# plcc44-to-dip44.net
KiCad netlist of a schematic drawn in EAGLE
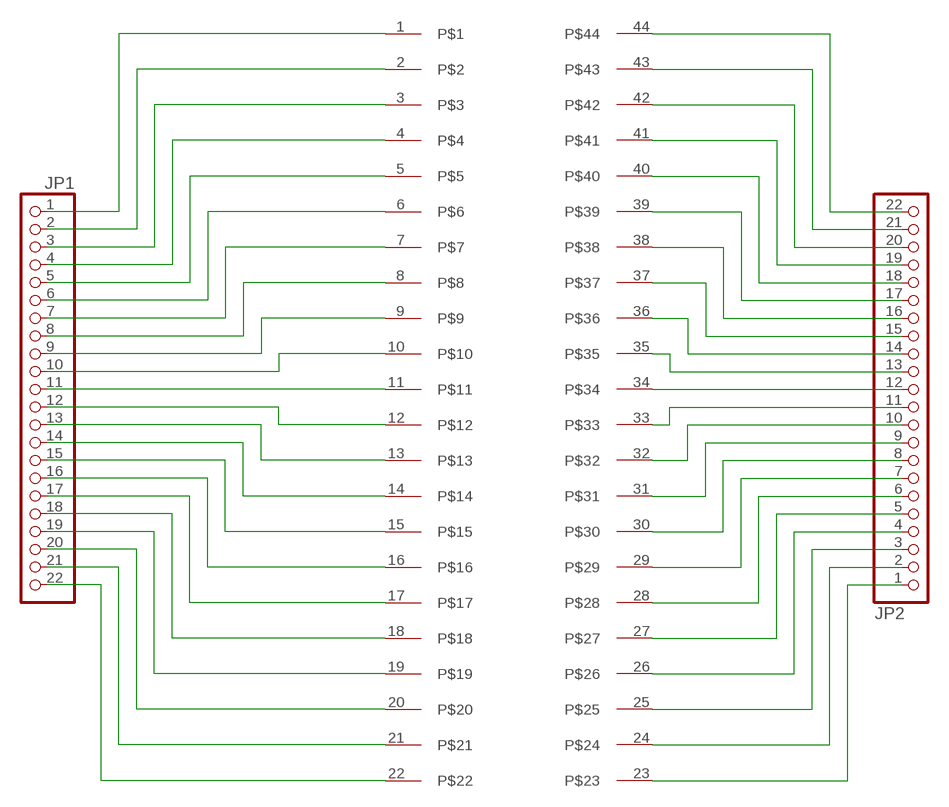
[diagram p0: schematic, sheet 1]

(export (version "E")
  (design (tool "Eeschema 10.0.6"))
  (components
    (comp (ref "JP1")
      (value "PINHD-1X22")
      (footprint "eagle-import:1X22")
      (libsource (lib "eagle-import") (part "PINHD-1X22"))
    )
    (comp (ref "JP2")
      (value "PINHD-1X22")
      (footprint "eagle-import:1X22")
      (libsource (lib "eagle-import") (part "PINHD-1X22"))
    )
    (comp (ref "U$1")
      (value "PLCC44-SOCKET")
      (footprint "eagle-import:S44")
      (libsource (lib "eagle-import") (part "PLCC44-SOCKET"))
    )
  )
  (nets
    (net (code "1") (name "Net-(U$1-P$1)") (class "Default")
      (node (ref "JP1") (pin "1") (pinfunction "1_1") (pintype "passive"))
      (node (ref "U$1") (pin "1") (pinfunction "P$1_1") (pintype "bidirectional"))
    )
    (net (code "2") (name "Net-(U$1-P$2)") (class "Default")
      (node (ref "JP1") (pin "2") (pinfunction "2_2") (pintype "passive"))
      (node (ref "U$1") (pin "2") (pinfunction "P$2_2") (pintype "bidirectional"))
    )
    (net (code "3") (name "Net-(U$1-P$3)") (class "Default")
      (node (ref "JP1") (pin "3") (pinfunction "3_3") (pintype "passive"))
      (node (ref "U$1") (pin "3") (pinfunction "P$3_3") (pintype "bidirectional"))
    )
    (net (code "4") (name "Net-(U$1-P$4)") (class "Default")
      (node (ref "JP1") (pin "4") (pinfunction "4_4") (pintype "passive"))
      (node (ref "U$1") (pin "4") (pinfunction "P$4_4") (pintype "bidirectional"))
    )
    (net (code "5") (name "Net-(U$1-P$5)") (class "Default")
      (node (ref "JP1") (pin "5") (pinfunction "5_5") (pintype "passive"))
      (node (ref "U$1") (pin "5") (pinfunction "P$5_5") (pintype "bidirectional"))
    )
    (net (code "6") (name "Net-(U$1-P$6)") (class "Default")
      (node (ref "JP1") (pin "6") (pinfunction "6_6") (pintype "passive"))
      (node (ref "U$1") (pin "6") (pinfunction "P$6_6") (pintype "bidirectional"))
    )
    (net (code "7") (name "Net-(U$1-P$7)") (class "Default")
      (node (ref "JP1") (pin "7") (pinfunction "7_7") (pintype "passive"))
      (node (ref "U$1") (pin "7") (pinfunction "P$7_7") (pintype "bidirectional"))
    )
    (net (code "8") (name "Net-(U$1-P$8)") (class "Default")
      (node (ref "JP1") (pin "8") (pinfunction "8_8") (pintype "passive"))
      (node (ref "U$1") (pin "8") (pinfunction "P$8_8") (pintype "bidirectional"))
    )
    (net (code "9") (name "Net-(U$1-P$9)") (class "Default")
      (node (ref "JP1") (pin "9") (pinfunction "9_9") (pintype "passive"))
      (node (ref "U$1") (pin "9") (pinfunction "P$9_9") (pintype "bidirectional"))
    )
    (net (code "10") (name "Net-(U$1-P$10)") (class "Default")
      (node (ref "JP1") (pin "10") (pinfunction "10_10") (pintype "passive"))
      (node (ref "U$1") (pin "10") (pinfunction "P$10_10") (pintype "bidirectional"))
    )
    (net (code "11") (name "Net-(U$1-P$11)") (class "Default")
      (node (ref "JP1") (pin "11") (pinfunction "11_11") (pintype "passive"))
      (node (ref "U$1") (pin "11") (pinfunction "P$11_11") (pintype "bidirectional"))
    )
    (net (code "12") (name "Net-(U$1-P$12)") (class "Default")
      (node (ref "JP1") (pin "12") (pinfunction "12_12") (pintype "passive"))
      (node (ref "U$1") (pin "12") (pinfunction "P$12_12") (pintype "bidirectional"))
    )
    (net (code "13") (name "Net-(U$1-P$13)") (class "Default")
      (node (ref "JP1") (pin "13") (pinfunction "13_13") (pintype "passive"))
      (node (ref "U$1") (pin "13") (pinfunction "P$13_13") (pintype "bidirectional"))
    )
    (net (code "14") (name "Net-(U$1-P$14)") (class "Default")
      (node (ref "JP1") (pin "14") (pinfunction "14_14") (pintype "passive"))
      (node (ref "U$1") (pin "14") (pinfunction "P$14_14") (pintype "bidirectional"))
    )
    (net (code "15") (name "Net-(U$1-P$15)") (class "Default")
      (node (ref "JP1") (pin "15") (pinfunction "15_15") (pintype "passive"))
      (node (ref "U$1") (pin "15") (pinfunction "P$15_15") (pintype "bidirectional"))
    )
    (net (code "16") (name "Net-(U$1-P$16)") (class "Default")
      (node (ref "JP1") (pin "16") (pinfunction "16_16") (pintype "passive"))
      (node (ref "U$1") (pin "16") (pinfunction "P$16_16") (pintype "bidirectional"))
    )
    (net (code "17") (name "Net-(U$1-P$17)") (class "Default")
      (node (ref "JP1") (pin "17") (pinfunction "17_17") (pintype "passive"))
      (node (ref "U$1") (pin "17") (pinfunction "P$17_17") (pintype "bidirectional"))
    )
    (net (code "18") (name "Net-(U$1-P$18)") (class "Default")
      (node (ref "JP1") (pin "18") (pinfunction "18_18") (pintype "passive"))
      (node (ref "U$1") (pin "18") (pinfunction "P$18_18") (pintype "bidirectional"))
    )
    (net (code "19") (name "Net-(U$1-P$19)") (class "Default")
      (node (ref "JP1") (pin "19") (pinfunction "19_19") (pintype "passive"))
      (node (ref "U$1") (pin "19") (pinfunction "P$19_19") (pintype "bidirectional"))
    )
    (net (code "20") (name "Net-(U$1-P$20)") (class "Default")
      (node (ref "JP1") (pin "20") (pinfunction "20_20") (pintype "passive"))
      (node (ref "U$1") (pin "20") (pinfunction "P$20_20") (pintype "bidirectional"))
    )
    (net (code "21") (name "Net-(U$1-P$21)") (class "Default")
      (node (ref "JP1") (pin "21") (pinfunction "21_21") (pintype "passive"))
      (node (ref "U$1") (pin "21") (pinfunction "P$21_21") (pintype "bidirectional"))
    )
    (net (code "22") (name "Net-(U$1-P$22)") (class "Default")
      (node (ref "JP1") (pin "22") (pinfunction "22_22") (pintype "passive"))
      (node (ref "U$1") (pin "22") (pinfunction "P$22_22") (pintype "bidirectional"))
    )
    (net (code "23") (name "Net-(U$1-P$23)") (class "Default")
      (node (ref "JP2") (pin "1") (pinfunction "1_1") (pintype "passive"))
      (node (ref "U$1") (pin "23") (pinfunction "P$23_23") (pintype "bidirectional"))
    )
    (net (code "24") (name "Net-(U$1-P$24)") (class "Default")
      (node (ref "JP2") (pin "2") (pinfunction "2_2") (pintype "passive"))
      (node (ref "U$1") (pin "24") (pinfunction "P$24_24") (pintype "bidirectional"))
    )
    (net (code "25") (name "Net-(U$1-P$25)") (class "Default")
      (node (ref "JP2") (pin "3") (pinfunction "3_3") (pintype "passive"))
      (node (ref "U$1") (pin "25") (pinfunction "P$25_25") (pintype "bidirectional"))
    )
    (net (code "26") (name "Net-(U$1-P$26)") (class "Default")
      (node (ref "JP2") (pin "4") (pinfunction "4_4") (pintype "passive"))
      (node (ref "U$1") (pin "26") (pinfunction "P$26_26") (pintype "bidirectional"))
    )
    (net (code "27") (name "Net-(U$1-P$27)") (class "Default")
      (node (ref "JP2") (pin "5") (pinfunction "5_5") (pintype "passive"))
      (node (ref "U$1") (pin "27") (pinfunction "P$27_27") (pintype "bidirectional"))
    )
    (net (code "28") (name "Net-(U$1-P$28)") (class "Default")
      (node (ref "JP2") (pin "6") (pinfunction "6_6") (pintype "passive"))
      (node (ref "U$1") (pin "28") (pinfunction "P$28_28") (pintype "bidirectional"))
    )
    (net (code "29") (name "Net-(U$1-P$29)") (class "Default")
      (node (ref "JP2") (pin "7") (pinfunction "7_7") (pintype "passive"))
      (node (ref "U$1") (pin "29") (pinfunction "P$29_29") (pintype "bidirectional"))
    )
    (net (code "30") (name "Net-(U$1-P$30)") (class "Default")
      (node (ref "JP2") (pin "8") (pinfunction "8_8") (pintype "passive"))
      (node (ref "U$1") (pin "30") (pinfunction "P$30_30") (pintype "bidirectional"))
    )
    (net (code "31") (name "Net-(U$1-P$31)") (class "Default")
      (node (ref "JP2") (pin "9") (pinfunction "9_9") (pintype "passive"))
      (node (ref "U$1") (pin "31") (pinfunction "P$31_31") (pintype "bidirectional"))
    )
    (net (code "32") (name "Net-(U$1-P$32)") (class "Default")
      (node (ref "JP2") (pin "10") (pinfunction "10_10") (pintype "passive"))
      (node (ref "U$1") (pin "32") (pinfunction "P$32_32") (pintype "bidirectional"))
    )
    (net (code "33") (name "Net-(U$1-P$33)") (class "Default")
      (node (ref "JP2") (pin "11") (pinfunction "11_11") (pintype "passive"))
      (node (ref "U$1") (pin "33") (pinfunction "P$33_33") (pintype "bidirectional"))
    )
    (net (code "34") (name "Net-(U$1-P$34)") (class "Default")
      (node (ref "JP2") (pin "12") (pinfunction "12_12") (pintype "passive"))
      (node (ref "U$1") (pin "34") (pinfunction "P$34_34") (pintype "bidirectional"))
    )
    (net (code "35") (name "Net-(U$1-P$35)") (class "Default")
      (node (ref "JP2") (pin "13") (pinfunction "13_13") (pintype "passive"))
      (node (ref "U$1") (pin "35") (pinfunction "P$35_35") (pintype "bidirectional"))
    )
    (net (code "36") (name "Net-(U$1-P$36)") (class "Default")
      (node (ref "JP2") (pin "14") (pinfunction "14_14") (pintype "passive"))
      (node (ref "U$1") (pin "36") (pinfunction "P$36_36") (pintype "bidirectional"))
    )
    (net (code "37") (name "Net-(U$1-P$37)") (class "Default")
      (node (ref "JP2") (pin "15") (pinfunction "15_15") (pintype "passive"))
      (node (ref "U$1") (pin "37") (pinfunction "P$37_37") (pintype "bidirectional"))
    )
    (net (code "38") (name "Net-(U$1-P$38)") (class "Default")
      (node (ref "JP2") (pin "16") (pinfunction "16_16") (pintype "passive"))
      (node (ref "U$1") (pin "38") (pinfunction "P$38_38") (pintype "bidirectional"))
    )
    (net (code "39") (name "Net-(U$1-P$39)") (class "Default")
      (node (ref "JP2") (pin "17") (pinfunction "17_17") (pintype "passive"))
      (node (ref "U$1") (pin "39") (pinfunction "P$39_39") (pintype "bidirectional"))
    )
    (net (code "40") (name "Net-(U$1-P$40)") (class "Default")
      (node (ref "JP2") (pin "18") (pinfunction "18_18") (pintype "passive"))
      (node (ref "U$1") (pin "40") (pinfunction "P$40_40") (pintype "bidirectional"))
    )
    (net (code "41") (name "Net-(U$1-P$41)") (class "Default")
      (node (ref "JP2") (pin "19") (pinfunction "19_19") (pintype "passive"))
      (node (ref "U$1") (pin "41") (pinfunction "P$41_41") (pintype "bidirectional"))
    )
    (net (code "42") (name "Net-(U$1-P$42)") (class "Default")
      (node (ref "JP2") (pin "20") (pinfunction "20_20") (pintype "passive"))
      (node (ref "U$1") (pin "42") (pinfunction "P$42_42") (pintype "bidirectional"))
    )
    (net (code "43") (name "Net-(U$1-P$43)") (class "Default")
      (node (ref "JP2") (pin "21") (pinfunction "21_21") (pintype "passive"))
      (node (ref "U$1") (pin "43") (pinfunction "P$43_43") (pintype "bidirectional"))
    )
    (net (code "44") (name "Net-(U$1-P$44)") (class "Default")
      (node (ref "JP2") (pin "22") (pinfunction "22_22") (pintype "passive"))
      (node (ref "U$1") (pin "44") (pinfunction "P$44_44") (pintype "bidirectional"))
    )
  )
)
